# Arduino_Ocelot.net
KiCad netlist of a schematic drawn in EAGLE
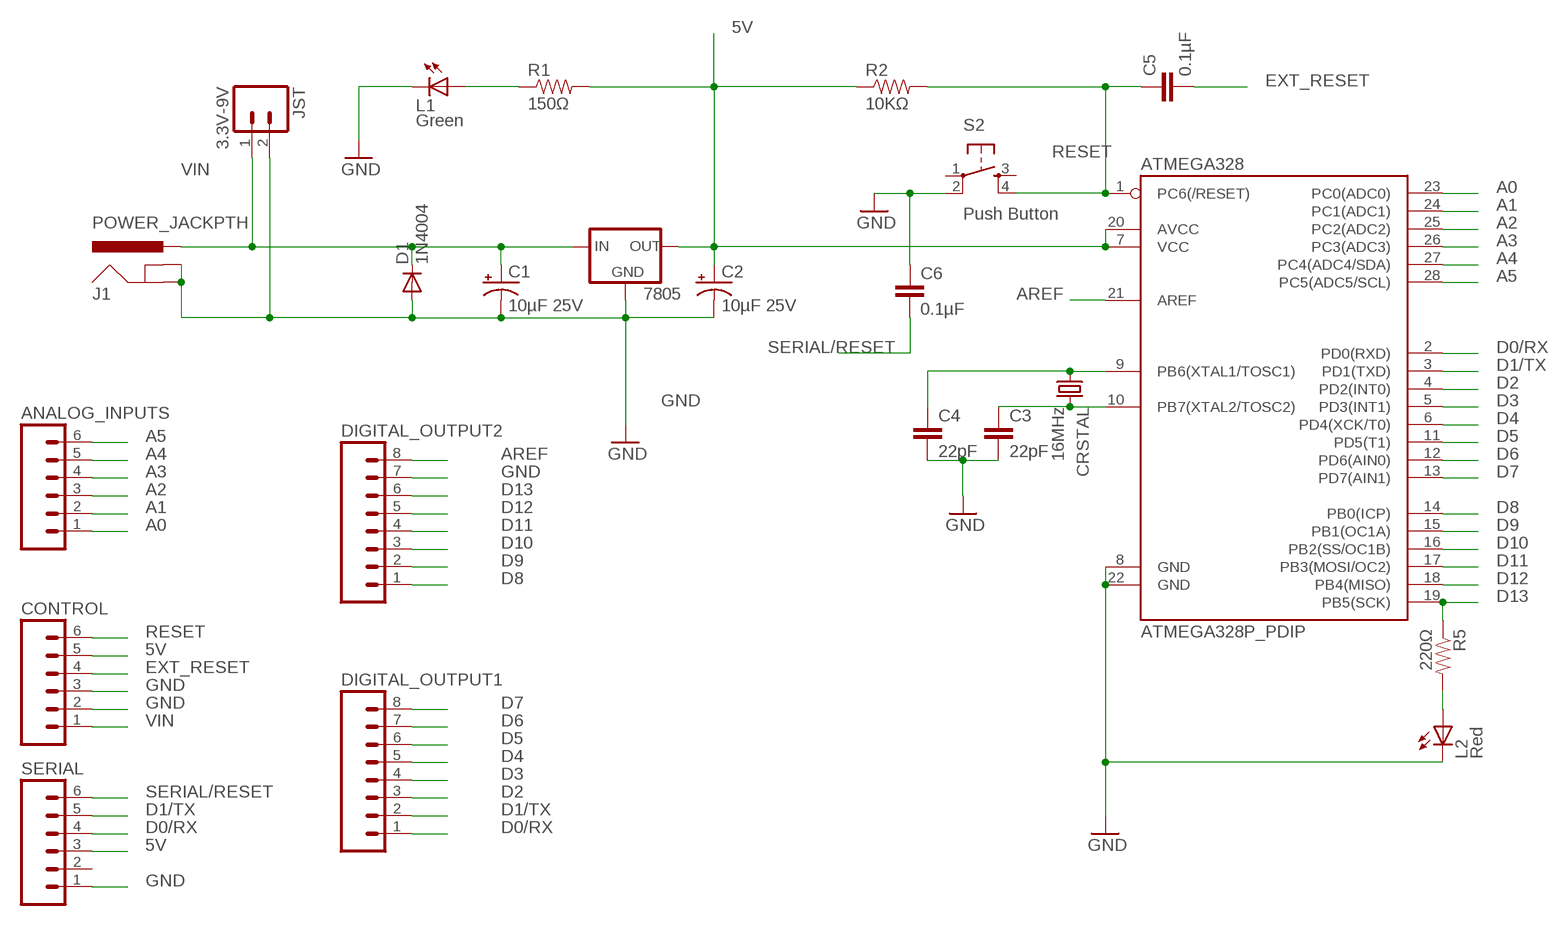
[diagram p0: schematic, sheet 1]

(export (version "E")
  (design (tool "Eeschema 10.0.6"))
  (components
    (comp (ref "7805")
      (value "V_REG_78XXTO-92_UNTESTED")
      (footprint "eagle-import:TO-92")
      (libsource (lib "eagle-import") (part "V_REG_78XXTO-92_UNTESTED"))
    )
    (comp (ref "ANALOG_INPUTS")
      (value "M06FEMALE_LOCK")
      (footprint "eagle-import:1X06_FEMALE_LOCK.010")
      (libsource (lib "eagle-import") (part "M06FEMALE_LOCK"))
    )
    (comp (ref "ATMEGA328")
      (value "ATMEGA328P_PDIP")
      (footprint "eagle-import:DIL28-3")
      (libsource (lib "eagle-import") (part "ATMEGA328P_PDIP"))
    )
    (comp (ref "C1")
      (value "10µF 25V")
      (footprint "eagle-import:CPOL-RADIAL-10UF-25V-KIT")
      (libsource (lib "eagle-import") (part "10UF-25V-20%(PTH)KIT"))
    )
    (comp (ref "C2")
      (value "10µF 25V")
      (footprint "eagle-import:CPOL-RADIAL-10UF-25V-KIT")
      (libsource (lib "eagle-import") (part "10UF-25V-20%(PTH)KIT"))
    )
    (comp (ref "C3")
      (value "22pF")
      (footprint "eagle-import:CAP-PTH-SMALL-KIT")
      (libsource (lib "eagle-import") (part "0.1UF-50V-20%(PTH)KIT-EZ"))
    )
    (comp (ref "C4")
      (value "22pF")
      (footprint "eagle-import:CAP-PTH-SMALL-KIT")
      (libsource (lib "eagle-import") (part "0.1UF-50V-20%(PTH)KIT-EZ"))
    )
    (comp (ref "C5")
      (value "0.1µF")
      (footprint "eagle-import:CAP-PTH-SMALL-KIT")
      (libsource (lib "eagle-import") (part "0.1UF-50V-20%(PTH)KIT-EZ"))
    )
    (comp (ref "C6")
      (value "0.1µF")
      (footprint "eagle-import:CAP-PTH-SMALL-KIT")
      (libsource (lib "eagle-import") (part "0.1UF-50V-20%(PTH)KIT-EZ"))
    )
    (comp (ref "CONTROL")
      (value "M06FEMALE_LOCK")
      (footprint "eagle-import:1X06_FEMALE_LOCK.010")
      (libsource (lib "eagle-import") (part "M06FEMALE_LOCK"))
    )
    (comp (ref "CRSTAL")
      (value "16MHz")
      (footprint "eagle-import:HC49US")
      (libsource (lib "eagle-import") (part "CRYSTALHC49US"))
    )
    (comp (ref "D1")
      (value "1N4004")
      (footprint "eagle-import:DIODE-1N4001-KIT")
      (libsource (lib "eagle-import") (part "DIODE"))
    )
    (comp (ref "DIGITAL_OUTPUT1")
      (value "M08NO_SILK")
      (footprint "eagle-import:1X08_NO_SILK")
      (libsource (lib "eagle-import") (part "M08NO_SILK"))
    )
    (comp (ref "DIGITAL_OUTPUT2")
      (value "M08NO_SILK")
      (footprint "eagle-import:1X08_NO_SILK")
      (libsource (lib "eagle-import") (part "M08NO_SILK"))
    )
    (comp (ref "J1")
      (value "POWER_JACKPTH")
      (footprint "eagle-import:POWER_JACK_PTH")
      (libsource (lib "eagle-import") (part "POWER_JACKPTH"))
    )
    (comp (ref "JST")
      (value "3.3V-9V")
      (footprint "eagle-import:JST-2-PTH-VERT")
      (libsource (lib "eagle-import") (part "M02JST-PTH-VERT"))
    )
    (comp (ref "L1")
      (value "Green")
      (footprint "eagle-import:LED3MM")
      (libsource (lib "eagle-import") (part "LED3MM"))
    )
    (comp (ref "L2")
      (value "Red")
      (footprint "eagle-import:LED3MM")
      (libsource (lib "eagle-import") (part "LED3MM"))
    )
    (comp (ref "R1")
      (value "150Ω")
      (footprint "eagle-import:AXIAL-0.4")
      (libsource (lib "eagle-import") (part "RESISTORPTH-1/4W"))
    )
    (comp (ref "R2")
      (value "10KΩ")
      (footprint "eagle-import:AXIAL-0.4")
      (libsource (lib "eagle-import") (part "RESISTORPTH-1/4W"))
    )
    (comp (ref "R5")
      (value "220Ω")
      (footprint "eagle-import:AXIAL-0.4")
      (libsource (lib "eagle-import") (part "RESISTORPTH-1/4W"))
    )
    (comp (ref "S2")
      (value "Push Button")
      (footprint "eagle-import:TACTILE-PTH")
      (libsource (lib "eagle-import") (part "TAC_SWITCHPTH"))
    )
    (comp (ref "SERIAL")
      (value "M06LOCK")
      (footprint "eagle-import:1X06_LOCK")
      (libsource (lib "eagle-import") (part "M06LOCK"))
    )
  )
  (nets
    (net (code "1") (name "/5V") (class "Default")
      (node (ref "7805") (pin "3") (pinfunction "OUT_3") (pintype "output"))
      (node (ref "ATMEGA328") (pin "20") (pinfunction "AVCC_20") (pintype "bidirectional"))
      (node (ref "ATMEGA328") (pin "7") (pinfunction "VCC_7") (pintype "bidirectional"))
      (node (ref "C2") (pin "1") (pinfunction "+_1") (pintype "passive"))
      (node (ref "CONTROL") (pin "5") (pinfunction "5_5") (pintype "passive"))
      (node (ref "R1") (pin "P$2") (pinfunction "2_P$2") (pintype "passive"))
      (node (ref "R2") (pin "P$1") (pinfunction "1_P$1") (pintype "passive"))
      (node (ref "SERIAL") (pin "3") (pinfunction "3_3") (pintype "passive"))
    )
    (net (code "2") (name "/A0") (class "Default")
      (node (ref "ANALOG_INPUTS") (pin "1") (pinfunction "1_1") (pintype "passive"))
      (node (ref "ATMEGA328") (pin "23") (pinfunction "PC0(ADC0)_23") (pintype "bidirectional"))
    )
    (net (code "3") (name "/A1") (class "Default")
      (node (ref "ANALOG_INPUTS") (pin "2") (pinfunction "2_2") (pintype "passive"))
      (node (ref "ATMEGA328") (pin "24") (pinfunction "PC1(ADC1)_24") (pintype "bidirectional"))
    )
    (net (code "4") (name "/A2") (class "Default")
      (node (ref "ANALOG_INPUTS") (pin "3") (pinfunction "3_3") (pintype "passive"))
      (node (ref "ATMEGA328") (pin "25") (pinfunction "PC2(ADC2)_25") (pintype "bidirectional"))
    )
    (net (code "5") (name "/A3") (class "Default")
      (node (ref "ANALOG_INPUTS") (pin "4") (pinfunction "4_4") (pintype "passive"))
      (node (ref "ATMEGA328") (pin "26") (pinfunction "PC3(ADC3)_26") (pintype "bidirectional"))
    )
    (net (code "6") (name "/A4") (class "Default")
      (node (ref "ANALOG_INPUTS") (pin "5") (pinfunction "5_5") (pintype "passive"))
      (node (ref "ATMEGA328") (pin "27") (pinfunction "PC4(ADC4/SDA)_27") (pintype "bidirectional"))
    )
    (net (code "7") (name "/A5") (class "Default")
      (node (ref "ANALOG_INPUTS") (pin "6") (pinfunction "6_6") (pintype "passive"))
      (node (ref "ATMEGA328") (pin "28") (pinfunction "PC5(ADC5/SCL)_28") (pintype "bidirectional"))
    )
    (net (code "8") (name "/AREF") (class "Default")
      (node (ref "ATMEGA328") (pin "21") (pinfunction "AREF_21") (pintype "bidirectional"))
      (node (ref "DIGITAL_OUTPUT2") (pin "8") (pinfunction "8_8") (pintype "passive"))
    )
    (net (code "9") (name "/D0{slash}RX") (class "Default")
      (node (ref "ATMEGA328") (pin "2") (pinfunction "PD0(RXD)_2") (pintype "bidirectional"))
      (node (ref "DIGITAL_OUTPUT1") (pin "1") (pinfunction "1_1") (pintype "passive"))
      (node (ref "SERIAL") (pin "4") (pinfunction "4_4") (pintype "passive"))
    )
    (net (code "10") (name "/D1{slash}TX") (class "Default")
      (node (ref "ATMEGA328") (pin "3") (pinfunction "PD1(TXD)_3") (pintype "bidirectional"))
      (node (ref "DIGITAL_OUTPUT1") (pin "2") (pinfunction "2_2") (pintype "passive"))
      (node (ref "SERIAL") (pin "5") (pinfunction "5_5") (pintype "passive"))
    )
    (net (code "11") (name "/D2") (class "Default")
      (node (ref "ATMEGA328") (pin "4") (pinfunction "PD2(INT0)_4") (pintype "bidirectional"))
      (node (ref "DIGITAL_OUTPUT1") (pin "3") (pinfunction "3_3") (pintype "passive"))
    )
    (net (code "12") (name "/D3") (class "Default")
      (node (ref "ATMEGA328") (pin "5") (pinfunction "PD3(INT1)_5") (pintype "bidirectional"))
      (node (ref "DIGITAL_OUTPUT1") (pin "4") (pinfunction "4_4") (pintype "passive"))
    )
    (net (code "13") (name "/D4") (class "Default")
      (node (ref "ATMEGA328") (pin "6") (pinfunction "PD4(XCK/T0)_6") (pintype "bidirectional"))
      (node (ref "DIGITAL_OUTPUT1") (pin "5") (pinfunction "5_5") (pintype "passive"))
    )
    (net (code "14") (name "/D5") (class "Default")
      (node (ref "ATMEGA328") (pin "11") (pinfunction "PD5(T1)_11") (pintype "bidirectional"))
      (node (ref "DIGITAL_OUTPUT1") (pin "6") (pinfunction "6_6") (pintype "passive"))
    )
    (net (code "15") (name "/D6") (class "Default")
      (node (ref "ATMEGA328") (pin "12") (pinfunction "PD6(AIN0)_12") (pintype "bidirectional"))
      (node (ref "DIGITAL_OUTPUT1") (pin "7") (pinfunction "7_7") (pintype "passive"))
    )
    (net (code "16") (name "/D7") (class "Default")
      (node (ref "ATMEGA328") (pin "13") (pinfunction "PD7(AIN1)_13") (pintype "bidirectional"))
      (node (ref "DIGITAL_OUTPUT1") (pin "8") (pinfunction "8_8") (pintype "passive"))
    )
    (net (code "17") (name "/D8") (class "Default")
      (node (ref "ATMEGA328") (pin "14") (pinfunction "PB0(ICP)_14") (pintype "bidirectional"))
      (node (ref "DIGITAL_OUTPUT2") (pin "1") (pinfunction "1_1") (pintype "passive"))
    )
    (net (code "18") (name "/D9") (class "Default")
      (node (ref "ATMEGA328") (pin "15") (pinfunction "PB1(OC1A)_15") (pintype "bidirectional"))
      (node (ref "DIGITAL_OUTPUT2") (pin "2") (pinfunction "2_2") (pintype "passive"))
    )
    (net (code "19") (name "/D10") (class "Default")
      (node (ref "ATMEGA328") (pin "16") (pinfunction "PB2(SS/OC1B)_16") (pintype "bidirectional"))
      (node (ref "DIGITAL_OUTPUT2") (pin "3") (pinfunction "3_3") (pintype "passive"))
    )
    (net (code "20") (name "/D11") (class "Default")
      (node (ref "ATMEGA328") (pin "17") (pinfunction "PB3(MOSI/OC2)_17") (pintype "bidirectional"))
      (node (ref "DIGITAL_OUTPUT2") (pin "4") (pinfunction "4_4") (pintype "passive"))
    )
    (net (code "21") (name "/D12") (class "Default")
      (node (ref "ATMEGA328") (pin "18") (pinfunction "PB4(MISO)_18") (pintype "bidirectional"))
      (node (ref "DIGITAL_OUTPUT2") (pin "5") (pinfunction "5_5") (pintype "passive"))
    )
    (net (code "22") (name "/D13") (class "Default")
      (node (ref "ATMEGA328") (pin "19") (pinfunction "PB5(SCK)_19") (pintype "bidirectional"))
      (node (ref "DIGITAL_OUTPUT2") (pin "6") (pinfunction "6_6") (pintype "passive"))
      (node (ref "R5") (pin "P$1") (pinfunction "1_P$1") (pintype "passive"))
    )
    (net (code "23") (name "/EXT_RESET") (class "Default")
      (node (ref "C5") (pin "2") (pinfunction "2_2") (pintype "passive"))
      (node (ref "CONTROL") (pin "4") (pinfunction "4_4") (pintype "passive"))
    )
    (net (code "24") (name "/RESET") (class "Default")
      (node (ref "ATMEGA328") (pin "1") (pinfunction "PC6(/RESET)_1") (pintype "bidirectional"))
      (node (ref "C5") (pin "1") (pinfunction "1_1") (pintype "passive"))
      (node (ref "CONTROL") (pin "6") (pinfunction "6_6") (pintype "passive"))
      (node (ref "R2") (pin "P$2") (pinfunction "2_P$2") (pintype "passive"))
      (node (ref "S2") (pin "4") (pinfunction "4_4") (pintype "passive"))
    )
    (net (code "25") (name "/SERIAL{slash}RESET") (class "Default")
      (node (ref "C6") (pin "2") (pinfunction "2_2") (pintype "passive"))
      (node (ref "SERIAL") (pin "6") (pinfunction "6_6") (pintype "passive"))
    )
    (net (code "26") (name "/VIN") (class "Default")
      (node (ref "7805") (pin "2") (pinfunction "IN_2") (pintype "input"))
      (node (ref "C1") (pin "1") (pinfunction "+_1") (pintype "passive"))
      (node (ref "CONTROL") (pin "1") (pinfunction "1_1") (pintype "passive"))
      (node (ref "D1") (pin "C") (pinfunction "C_C") (pintype "passive"))
      (node (ref "J1") (pin "PWR") (pinfunction "PWR_PWR") (pintype "bidirectional"))
      (node (ref "JST") (pin "1") (pinfunction "1_1") (pintype "passive"))
    )
    (net (code "27") (name "GND") (class "Default")
      (node (ref "7805") (pin "1") (pinfunction "GND_1") (pintype "input"))
      (node (ref "ATMEGA328") (pin "22") (pinfunction "GND_22") (pintype "bidirectional"))
      (node (ref "ATMEGA328") (pin "8") (pinfunction "GND_8") (pintype "bidirectional"))
      (node (ref "C1") (pin "2") (pinfunction "-_2") (pintype "passive"))
      (node (ref "C2") (pin "2") (pinfunction "-_2") (pintype "passive"))
      (node (ref "C3") (pin "2") (pinfunction "2_2") (pintype "passive"))
      (node (ref "C4") (pin "2") (pinfunction "2_2") (pintype "passive"))
      (node (ref "C6") (pin "1") (pinfunction "1_1") (pintype "passive"))
      (node (ref "CONTROL") (pin "2") (pinfunction "2_2") (pintype "passive"))
      (node (ref "CONTROL") (pin "3") (pinfunction "3_3") (pintype "passive"))
      (node (ref "D1") (pin "A") (pinfunction "A_A") (pintype "passive"))
      (node (ref "DIGITAL_OUTPUT2") (pin "7") (pinfunction "7_7") (pintype "passive"))
      (node (ref "J1") (pin "GND") (pinfunction "GND_GND") (pintype "bidirectional"))
      (node (ref "J1") (pin "GNDBREAK") (pinfunction "GNDBREAK_GNDBREAK") (pintype "bidirectional"))
      (node (ref "JST") (pin "2") (pinfunction "2_2") (pintype "passive"))
      (node (ref "L1") (pin "K") (pinfunction "C_K") (pintype "passive"))
      (node (ref "L2") (pin "K") (pinfunction "C_K") (pintype "passive"))
      (node (ref "S2") (pin "2") (pinfunction "2_2") (pintype "passive"))
      (node (ref "SERIAL") (pin "1") (pinfunction "1_1") (pintype "passive"))
    )
    (net (code "28") (name "Net-(ATMEGA328-PB6(XTAL1{slash}TOSC1))") (class "Default")
      (node (ref "ATMEGA328") (pin "9") (pinfunction "PB6(XTAL1/TOSC1)_9") (pintype "bidirectional"))
      (node (ref "C4") (pin "1") (pinfunction "1_1") (pintype "passive"))
      (node (ref "CRSTAL") (pin "1") (pinfunction "1_1") (pintype "passive"))
    )
    (net (code "29") (name "Net-(ATMEGA328-PB7(XTAL2{slash}TOSC2))") (class "Default")
      (node (ref "ATMEGA328") (pin "10") (pinfunction "PB7(XTAL2/TOSC2)_10") (pintype "bidirectional"))
      (node (ref "C3") (pin "1") (pinfunction "1_1") (pintype "passive"))
      (node (ref "CRSTAL") (pin "2") (pinfunction "2_2") (pintype "passive"))
    )
    (net (code "30") (name "Net-(R1-1)") (class "Default")
      (node (ref "L1") (pin "A") (pinfunction "A_A") (pintype "passive"))
      (node (ref "R1") (pin "P$1") (pinfunction "1_P$1") (pintype "passive"))
    )
    (net (code "31") (name "Net-(R5-2)") (class "Default")
      (node (ref "L2") (pin "A") (pinfunction "A_A") (pintype "passive"))
      (node (ref "R5") (pin "P$2") (pinfunction "2_P$2") (pintype "passive"))
    )
    (net (code "32") (name "unconnected-(S2-Pad1)") (class "Default")
      (node (ref "S2") (pin "1") (pinfunction "1_1") (pintype "passive"))
    )
    (net (code "33") (name "unconnected-(S2-Pad3)") (class "Default")
      (node (ref "S2") (pin "3") (pinfunction "3_3") (pintype "passive"))
    )
    (net (code "34") (name "unconnected-(SERIAL-Pad2)") (class "Default")
      (node (ref "SERIAL") (pin "2") (pinfunction "2_2") (pintype "passive"))
    )
  )
)
